# MICROCONTROLER.net
KiCad netlist of a schematic drawn in Altium Designer
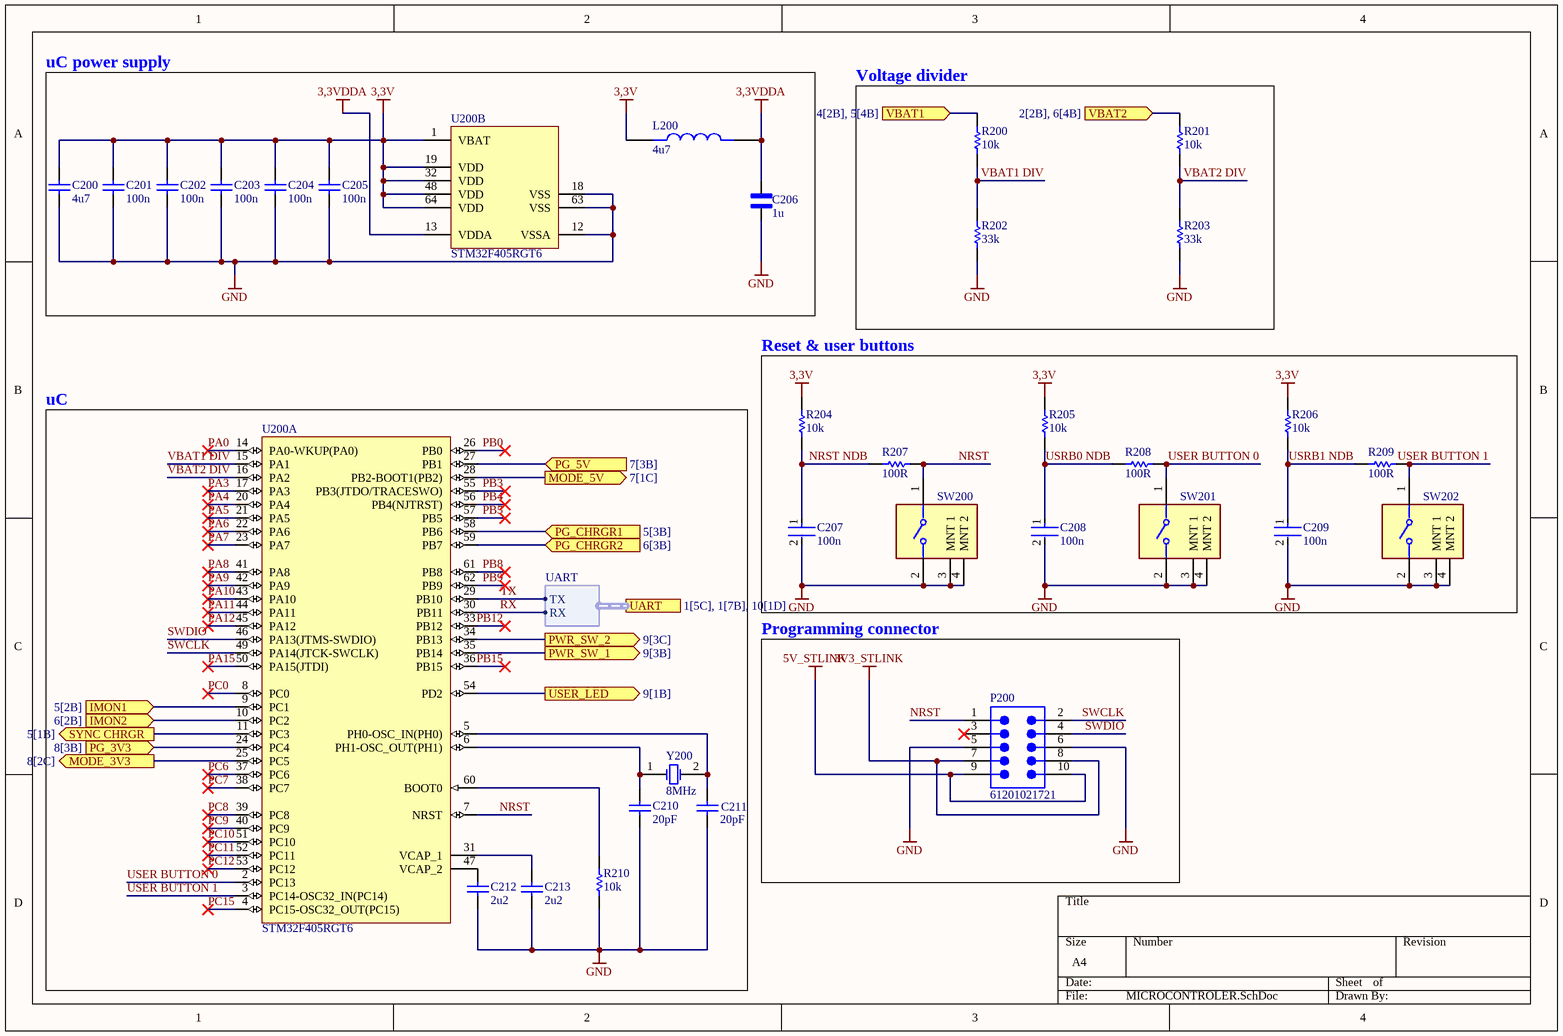
[diagram p0: MICROCONTROLER.SchDoc]

(export (version "E")
  (design (tool "Eeschema 10.0.6"))
  (components
    (comp (ref "C200")
      (value "4u7")
      (footprint "CAPC1005X55X30LL05T10")
      (fields (field (name "MANUFACTURER") "Kemet") (field (name "PART NUMBER") "C0402C104K4RACTU"))
      (libsource (lib "Altium Content Vault") (part "CAP"))
    )
    (comp (ref "C201")
      (value "100n")
      (footprint "CAPC1005X55X30LL05T10")
      (fields (field (name "MANUFACTURER") "Kemet") (field (name "PART NUMBER") "C0402C104K4RACTU"))
      (libsource (lib "Altium Content Vault") (part "CAP"))
    )
    (comp (ref "C202")
      (value "100n")
      (footprint "CAPC1005X55X30LL05T10")
      (fields (field (name "MANUFACTURER") "Kemet") (field (name "PART NUMBER") "C0402C104K4RACTU"))
      (libsource (lib "Altium Content Vault") (part "CAP"))
    )
    (comp (ref "C203")
      (value "100n")
      (footprint "CAPC1005X55X30LL05T10")
      (fields (field (name "MANUFACTURER") "Kemet") (field (name "PART NUMBER") "C0402C104K4RACTU"))
      (libsource (lib "Altium Content Vault") (part "CAP"))
    )
    (comp (ref "C204")
      (value "100n")
      (footprint "CAPC1005X55X30LL05T10")
      (fields (field (name "MANUFACTURER") "Kemet") (field (name "PART NUMBER") "C0402C104K4RACTU"))
      (libsource (lib "Altium Content Vault") (part "CAP"))
    )
    (comp (ref "C205")
      (value "100n")
      (footprint "CAPC1005X55X30LL05T10")
      (fields (field (name "MANUFACTURER") "Kemet") (field (name "PART NUMBER") "C0402C104K4RACTU"))
      (libsource (lib "Altium Content Vault") (part "CAP"))
    )
    (comp (ref "C206")
      (value "1u")
      (footprint "CAPC1005X70N")
      (fields (field (name "MF") "Taiyo Yuden") (field (name "MP") "MAASL105CD7105MFCA01"))
      (libsource (lib "C_1u") (part "MAASL105CD7105MFCA01"))
    )
    (comp (ref "C207")
      (value "100n")
      (footprint "FP-C0402-BB-MFG")
      (description "CAP CER 0.1UF 10V X5R 0402")
      (fields (field (name "MANUFACTURER") "Kemet") (field (name "TOLERANCE") "0.1"))
      (libsource (lib "Altium Content Vault") (part "b4654b650e69147ec39a6b967a45e02"))
    )
    (comp (ref "C208")
      (value "100n")
      (footprint "FP-C0402-BB-MFG")
      (description "CAP CER 0.1UF 10V X5R 0402")
      (fields (field (name "MANUFACTURER") "Kemet") (field (name "TOLERANCE") "0.1"))
      (libsource (lib "Altium Content Vault") (part "b4654b650e69147ec39a6b967a45e02"))
    )
    (comp (ref "C209")
      (value "100n")
      (footprint "FP-C0402-BB-MFG")
      (description "CAP CER 0.1UF 10V X5R 0402")
      (fields (field (name "MANUFACTURER") "Kemet") (field (name "TOLERANCE") "0.1"))
      (libsource (lib "Altium Content Vault") (part "b4654b650e69147ec39a6b967a45e02"))
    )
    (comp (ref "C210")
      (value "20pF")
      (footprint "tu 0805")
      (description "Dán")
      (libsource (lib "Capacitor") (part "Tu 0805 20pF 50V 10%"))
    )
    (comp (ref "C211")
      (value "20pF")
      (footprint "tu 0805")
      (description "Dán")
      (libsource (lib "Capacitor") (part "Tu 0805 20pF 50V 10%"))
    )
    (comp (ref "C212")
      (value "2u2")
      (footprint "tu 0805")
      (description "Dán")
      (libsource (lib "Capacitor") (part "Tu 0805 225 25V 10%"))
    )
    (comp (ref "C213")
      (value "2u2")
      (footprint "tu 0805")
      (description "Dán")
      (libsource (lib "Capacitor") (part "Tu 0805 225 25V 10%"))
    )
    (comp (ref "L200")
      (value "4u7")
      (footprint "INDC2012X100N")
      (description "Surface Mount High Frequency Inductor, MLP Series, 4.7 H, 20%, 0805 [2012 Metric], 0.26 ohm")
      (fields (field (name "MF") "TDK") (field (name "MP") "MLP2012S4R7MT0S1"))
      (libsource (lib "L4u7") (part "MLP2012S4R7MT0S1"))
    )
    (comp (ref "P200")
      (value "61201021721")
      (footprint "61201021721")
      (libsource (lib "Altium Content Vault") (part "Header_Male_2R_10P"))
    )
    (comp (ref "R200")
      (value "10k")
      (footprint "RESC1609X50X30NL8T20")
      (description "Chip Resistor, 10 KOhm, +/- 1%, 100 mW, -55 to 155 degC, 0603 (1608 Metric), RoHS, Tape and Reel")
      (fields (field (name "MANUFACTURER") "Vishay Semiconductor"))
      (libsource (lib "Altium Content Vault") (part "RES-2"))
    )
    (comp (ref "R201")
      (value "10k")
      (footprint "RESC1609X50X30NL8T20")
      (description "Chip Resistor, 10 KOhm, +/- 1%, 100 mW, -55 to 155 degC, 0603 (1608 Metric), RoHS, Tape and Reel")
      (fields (field (name "MANUFACTURER") "Vishay Semiconductor"))
      (libsource (lib "Altium Content Vault") (part "RES-2"))
    )
    (comp (ref "R202")
      (value "33k")
      (footprint "RESC1005X40X25ML05T10")
      (fields (field (name "PART NUMBER") "RC0402FR-0733KL") (field (name "MANUFACTURER") "Yageo / Phycomp"))
      (libsource (lib "Altium Content Vault") (part "RES"))
    )
    (comp (ref "R203")
      (value "33k")
      (footprint "RESC1005X40X25ML05T10")
      (fields (field (name "PART NUMBER") "RC0402FR-0733KL") (field (name "MANUFACTURER") "Yageo / Phycomp"))
      (libsource (lib "Altium Content Vault") (part "RES"))
    )
    (comp (ref "R204")
      (value "10k")
      (footprint "RESC1609X50X30NL8T20")
      (description "Chip Resistor, 10 KOhm, +/- 1%, 100 mW, -55 to 155 degC, 0603 (1608 Metric), RoHS, Tape and Reel")
      (fields (field (name "MANUFACTURER") "Vishay Semiconductor"))
      (libsource (lib "Altium Content Vault") (part "RES-2"))
    )
    (comp (ref "R205")
      (value "10k")
      (footprint "RESC1609X50X30NL8T20")
      (description "Chip Resistor, 10 KOhm, +/- 1%, 100 mW, -55 to 155 degC, 0603 (1608 Metric), RoHS, Tape and Reel")
      (fields (field (name "MANUFACTURER") "Vishay Semiconductor"))
      (libsource (lib "Altium Content Vault") (part "RES-2"))
    )
    (comp (ref "R206")
      (value "10k")
      (footprint "RESC1609X50X30NL8T20")
      (description "Chip Resistor, 10 KOhm, +/- 1%, 100 mW, -55 to 155 degC, 0603 (1608 Metric), RoHS, Tape and Reel")
      (fields (field (name "MANUFACTURER") "Vishay Semiconductor"))
      (libsource (lib "Altium Content Vault") (part "RES-2"))
    )
    (comp (ref "R207")
      (value "100R")
      (footprint "RESC1005X40X25ML05T10")
      (fields (field (name "PART NUMBER") "RC0402FR-07100RL") (field (name "MANUFACTURER") "Yageo / Phycomp"))
      (libsource (lib "Altium Content Vault") (part "RES"))
    )
    (comp (ref "R208")
      (value "100R")
      (footprint "RESC1005X40X25ML05T10")
      (fields (field (name "PART NUMBER") "RC0402FR-07100RL") (field (name "MANUFACTURER") "Yageo / Phycomp"))
      (libsource (lib "Altium Content Vault") (part "RES"))
    )
    (comp (ref "R209")
      (value "100R")
      (footprint "RESC1005X40X25ML05T10")
      (fields (field (name "PART NUMBER") "RC0402FR-07100RL") (field (name "MANUFACTURER") "Yageo / Phycomp"))
      (libsource (lib "Altium Content Vault") (part "RES"))
    )
    (comp (ref "R210")
      (value "10k")
      (footprint "RESC1609X50X30NL8T20")
      (description "Chip Resistor, 10 KOhm, +/- 1%, 100 mW, -55 to 155 degC, 0603 (1608 Metric), RoHS, Tape and Reel")
      (fields (field (name "MANUFACTURER") "Vishay Semiconductor"))
      (libsource (lib "Altium Content Vault") (part "RES-2"))
    )
    (comp (ref "SW200")
      (value "B3F-3152")
      (footprint "FP-B3F-3152-MFG")
      (description "SWITCH TACTILE SPST-NO 0.05A 24V")
      (libsource (lib "Altium Content Vault") (part "ed2974a2078be5bbdf800c999931250"))
    )
    (comp (ref "SW201")
      (value "B3F-3152")
      (footprint "FP-B3F-3152-MFG")
      (description "SWITCH TACTILE SPST-NO 0.05A 24V")
      (libsource (lib "Altium Content Vault") (part "ed2974a2078be5bbdf800c999931250"))
    )
    (comp (ref "SW202")
      (value "B3F-3152")
      (footprint "FP-B3F-3152-MFG")
      (description "SWITCH TACTILE SPST-NO 0.05A 24V")
      (libsource (lib "Altium Content Vault") (part "ed2974a2078be5bbdf800c999931250"))
    )
    (comp (ref "U200")
      (value "STM32F405RGT6")
      (footprint "STM-LQFP64_N")
      (fields (field (name "MANUFACTURER") "STMicroelectronics"))
      (libsource (lib "Altium Content Vault") (part "MC-ARM-STM32F4X5-SQ64"))
    )
    (comp (ref "Y200")
      (value "8MHz")
      (footprint "ABRA-ABLS-14.7456MHZ-B2-T_V")
      (description "Low Profile Crystal, 8.0 MHz, +/- 30 ppm, -20 to 70 degC, 2-Pin SMD, RoHS, Tape and Reel")
      (fields (field (name "MANUFACTURER") "ABRACON") (field (name "TOLERANCE") "30PPM"))
      (libsource (lib "Altium Content Vault") (part "XTAL_1-2-2"))
    )
  )
  (nets
    (net (code "2") (name "/IMON1") (class "Default")
      (node (ref "U200") (pin "9") (pinfunction "PC1_9") (pintype "bidirectional"))
    )
    (net (code "3") (name "/IMON2") (class "Default")
      (node (ref "U200") (pin "10") (pinfunction "PC2_10") (pintype "bidirectional"))
    )
    (net (code "4") (name "/MODE_3V3") (class "Default")
      (node (ref "U200") (pin "25") (pinfunction "PC5_25") (pintype "bidirectional"))
    )
    (net (code "5") (name "/MODE_5V") (class "Default")
      (node (ref "U200") (pin "28") (pinfunction "PB2-BOOT1(PB2)_28") (pintype "bidirectional"))
    )
    (net (code "6") (name "/NRST") (class "Default")
      (node (ref "P200") (pin "1") (pinfunction "1_1") (pintype "passive"))
      (node (ref "R207") (pin "2") (pinfunction "2_2") (pintype "passive"))
      (node (ref "SW200") (pin "1") (pinfunction "1_1") (pintype "passive"))
      (node (ref "U200") (pin "7") (pinfunction "NRST_7") (pintype "bidirectional"))
    )
    (net (code "7") (name "/NRST NDB") (class "Default")
      (node (ref "C207") (pin "1") (pinfunction "1_1") (pintype "passive"))
      (node (ref "R204") (pin "1") (pinfunction "1_1") (pintype "passive"))
      (node (ref "R207") (pin "1") (pinfunction "1_1") (pintype "passive"))
    )
    (net (code "8") (name "/PA0") (class "Default")
      (node (ref "U200") (pin "14") (pinfunction "PA0-WKUP(PA0)_14") (pintype "bidirectional+no_connect"))
    )
    (net (code "9") (name "/PA3") (class "Default")
      (node (ref "U200") (pin "17") (pinfunction "PA3_17") (pintype "bidirectional+no_connect"))
    )
    (net (code "10") (name "/PA4") (class "Default")
      (node (ref "U200") (pin "20") (pinfunction "PA4_20") (pintype "bidirectional+no_connect"))
    )
    (net (code "11") (name "/PA5") (class "Default")
      (node (ref "U200") (pin "21") (pinfunction "PA5_21") (pintype "bidirectional+no_connect"))
    )
    (net (code "12") (name "/PA6") (class "Default")
      (node (ref "U200") (pin "22") (pinfunction "PA6_22") (pintype "bidirectional+no_connect"))
    )
    (net (code "13") (name "/PA7") (class "Default")
      (node (ref "U200") (pin "23") (pinfunction "PA7_23") (pintype "bidirectional+no_connect"))
    )
    (net (code "14") (name "/PA8") (class "Default")
      (node (ref "U200") (pin "41") (pinfunction "PA8_41") (pintype "bidirectional+no_connect"))
    )
    (net (code "15") (name "/PA9") (class "Default")
      (node (ref "U200") (pin "42") (pinfunction "PA9_42") (pintype "bidirectional+no_connect"))
    )
    (net (code "16") (name "/PA10") (class "Default")
      (node (ref "U200") (pin "43") (pinfunction "PA10_43") (pintype "bidirectional+no_connect"))
    )
    (net (code "17") (name "/PA11") (class "Default")
      (node (ref "U200") (pin "44") (pinfunction "PA11_44") (pintype "bidirectional+no_connect"))
    )
    (net (code "18") (name "/PA12") (class "Default")
      (node (ref "U200") (pin "45") (pinfunction "PA12_45") (pintype "bidirectional+no_connect"))
    )
    (net (code "19") (name "/PA15") (class "Default")
      (node (ref "U200") (pin "50") (pinfunction "PA15(JTDI)_50") (pintype "bidirectional+no_connect"))
    )
    (net (code "20") (name "/PB0") (class "Default")
      (node (ref "U200") (pin "26") (pinfunction "PB0_26") (pintype "bidirectional+no_connect"))
    )
    (net (code "21") (name "/PB3") (class "Default")
      (node (ref "U200") (pin "55") (pinfunction "PB3(JTDO/TRACESWO)_55") (pintype "bidirectional+no_connect"))
    )
    (net (code "22") (name "/PB4") (class "Default")
      (node (ref "U200") (pin "56") (pinfunction "PB4(NJTRST)_56") (pintype "bidirectional+no_connect"))
    )
    (net (code "23") (name "/PB5") (class "Default")
      (node (ref "U200") (pin "57") (pinfunction "PB5_57") (pintype "bidirectional+no_connect"))
    )
    (net (code "24") (name "/PB8") (class "Default")
      (node (ref "U200") (pin "61") (pinfunction "PB8_61") (pintype "bidirectional+no_connect"))
    )
    (net (code "25") (name "/PB9") (class "Default")
      (node (ref "U200") (pin "62") (pinfunction "PB9_62") (pintype "bidirectional+no_connect"))
    )
    (net (code "26") (name "/PB12") (class "Default")
      (node (ref "U200") (pin "33") (pinfunction "PB12_33") (pintype "bidirectional+no_connect"))
    )
    (net (code "27") (name "/PB15") (class "Default")
      (node (ref "U200") (pin "36") (pinfunction "PB15_36") (pintype "bidirectional+no_connect"))
    )
    (net (code "28") (name "/PC0") (class "Default")
      (node (ref "U200") (pin "8") (pinfunction "PC0_8") (pintype "bidirectional+no_connect"))
    )
    (net (code "29") (name "/PC6") (class "Default")
      (node (ref "U200") (pin "37") (pinfunction "PC6_37") (pintype "bidirectional+no_connect"))
    )
    (net (code "30") (name "/PC7") (class "Default")
      (node (ref "U200") (pin "38") (pinfunction "PC7_38") (pintype "bidirectional+no_connect"))
    )
    (net (code "31") (name "/PC8") (class "Default")
      (node (ref "U200") (pin "39") (pinfunction "PC8_39") (pintype "bidirectional+no_connect"))
    )
    (net (code "32") (name "/PC9") (class "Default")
      (node (ref "U200") (pin "40") (pinfunction "PC9_40") (pintype "bidirectional+no_connect"))
    )
    (net (code "33") (name "/PC10") (class "Default")
      (node (ref "U200") (pin "51") (pinfunction "PC10_51") (pintype "bidirectional+no_connect"))
    )
    (net (code "34") (name "/PC11") (class "Default")
      (node (ref "U200") (pin "52") (pinfunction "PC11_52") (pintype "bidirectional+no_connect"))
    )
    (net (code "35") (name "/PC12") (class "Default")
      (node (ref "U200") (pin "53") (pinfunction "PC12_53") (pintype "bidirectional+no_connect"))
    )
    (net (code "36") (name "/PC15") (class "Default")
      (node (ref "U200") (pin "4") (pinfunction "PC15-OSC32_OUT(PC15)_4") (pintype "bidirectional+no_connect"))
    )
    (net (code "37") (name "/PG_3V3") (class "Default")
      (node (ref "U200") (pin "24") (pinfunction "PC4_24") (pintype "bidirectional"))
    )
    (net (code "38") (name "/PG_5V") (class "Default")
      (node (ref "U200") (pin "27") (pinfunction "PB1_27") (pintype "bidirectional"))
    )
    (net (code "39") (name "/PG_CHRGR1") (class "Default")
      (node (ref "U200") (pin "58") (pinfunction "PB6_58") (pintype "bidirectional"))
    )
    (net (code "40") (name "/PG_CHRGR2") (class "Default")
      (node (ref "U200") (pin "59") (pinfunction "PB7_59") (pintype "bidirectional"))
    )
    (net (code "41") (name "/PWR_SW_1") (class "Default")
      (node (ref "U200") (pin "35") (pinfunction "PB14_35") (pintype "bidirectional"))
    )
    (net (code "42") (name "/PWR_SW_2") (class "Default")
      (node (ref "U200") (pin "34") (pinfunction "PB13_34") (pintype "bidirectional"))
    )
    (net (code "43") (name "/RX") (class "Default")
      (node (ref "U200") (pin "30") (pinfunction "PB11_30") (pintype "bidirectional"))
    )
    (net (code "44") (name "/SWCLK") (class "Default")
      (node (ref "P200") (pin "2") (pinfunction "2_2") (pintype "passive"))
      (node (ref "U200") (pin "49") (pinfunction "PA14(JTCK-SWCLK)_49") (pintype "bidirectional"))
    )
    (net (code "45") (name "/SWDIO") (class "Default")
      (node (ref "P200") (pin "4") (pinfunction "4_4") (pintype "passive"))
      (node (ref "U200") (pin "46") (pinfunction "PA13(JTMS-SWDIO)_46") (pintype "bidirectional"))
    )
    (net (code "46") (name "/SYNC CHRGR") (class "Default")
      (node (ref "U200") (pin "11") (pinfunction "PC3_11") (pintype "bidirectional"))
    )
    (net (code "47") (name "/TX") (class "Default")
      (node (ref "U200") (pin "29") (pinfunction "PB10_29") (pintype "bidirectional"))
    )
    (net (code "48") (name "/USER BUTTON 0") (class "Default")
      (node (ref "R208") (pin "2") (pinfunction "2_2") (pintype "passive"))
      (node (ref "SW201") (pin "1") (pinfunction "1_1") (pintype "passive"))
      (node (ref "U200") (pin "2") (pinfunction "PC13_2") (pintype "bidirectional"))
    )
    (net (code "49") (name "/USER BUTTON 1") (class "Default")
      (node (ref "R209") (pin "2") (pinfunction "2_2") (pintype "passive"))
      (node (ref "SW202") (pin "1") (pinfunction "1_1") (pintype "passive"))
      (node (ref "U200") (pin "3") (pinfunction "PC14-OSC32_IN(PC14)_3") (pintype "bidirectional"))
    )
    (net (code "50") (name "/USER_LED") (class "Default")
      (node (ref "U200") (pin "54") (pinfunction "PD2_54") (pintype "bidirectional"))
    )
    (net (code "51") (name "/USRB0 NDB") (class "Default")
      (node (ref "C208") (pin "1") (pinfunction "1_1") (pintype "passive"))
      (node (ref "R205") (pin "1") (pinfunction "1_1") (pintype "passive"))
      (node (ref "R208") (pin "1") (pinfunction "1_1") (pintype "passive"))
    )
    (net (code "52") (name "/USRB1 NDB") (class "Default")
      (node (ref "C209") (pin "1") (pinfunction "1_1") (pintype "passive"))
      (node (ref "R206") (pin "1") (pinfunction "1_1") (pintype "passive"))
      (node (ref "R209") (pin "1") (pinfunction "1_1") (pintype "passive"))
    )
    (net (code "53") (name "/VBAT1") (class "Default")
      (node (ref "R200") (pin "2") (pinfunction "2_2") (pintype "passive"))
    )
    (net (code "54") (name "/VBAT1 DIV") (class "Default")
      (node (ref "R200") (pin "1") (pinfunction "1_1") (pintype "passive"))
      (node (ref "R202") (pin "2") (pinfunction "2_2") (pintype "passive"))
      (node (ref "U200") (pin "15") (pinfunction "PA1_15") (pintype "bidirectional"))
    )
    (net (code "55") (name "/VBAT2") (class "Default")
      (node (ref "R201") (pin "2") (pinfunction "2_2") (pintype "passive"))
    )
    (net (code "56") (name "/VBAT2 DIV") (class "Default")
      (node (ref "R201") (pin "1") (pinfunction "1_1") (pintype "passive"))
      (node (ref "R203") (pin "2") (pinfunction "2_2") (pintype "passive"))
      (node (ref "U200") (pin "16") (pinfunction "PA2_16") (pintype "bidirectional"))
    )
    (net (code "58") (name "3,3V") (class "Default")
      (node (ref "C200") (pin "2") (pinfunction "2_2") (pintype "passive"))
      (node (ref "C201") (pin "2") (pinfunction "2_2") (pintype "passive"))
      (node (ref "C202") (pin "2") (pinfunction "2_2") (pintype "passive"))
      (node (ref "C203") (pin "2") (pinfunction "2_2") (pintype "passive"))
      (node (ref "C204") (pin "2") (pinfunction "2_2") (pintype "passive"))
      (node (ref "C205") (pin "2") (pinfunction "2_2") (pintype "passive"))
      (node (ref "L200") (pin "1") (pinfunction "1_1") (pintype "passive"))
      (node (ref "R204") (pin "2") (pinfunction "2_2") (pintype "passive"))
      (node (ref "R205") (pin "2") (pinfunction "2_2") (pintype "passive"))
      (node (ref "R206") (pin "2") (pinfunction "2_2") (pintype "passive"))
      (node (ref "U200") (pin "1") (pinfunction "VBAT_1") (pintype "power_in"))
      (node (ref "U200") (pin "19") (pinfunction "VDD_19") (pintype "power_in"))
      (node (ref "U200") (pin "32") (pinfunction "VDD_32") (pintype "power_in"))
      (node (ref "U200") (pin "48") (pinfunction "VDD_48") (pintype "power_in"))
      (node (ref "U200") (pin "64") (pinfunction "VDD_64") (pintype "power_in"))
    )
    (net (code "59") (name "3,3VDDA") (class "Default")
      (node (ref "C206") (pin "2") (pinfunction "2_2") (pintype "passive"))
      (node (ref "L200") (pin "2") (pinfunction "2_2") (pintype "passive"))
      (node (ref "U200") (pin "13") (pinfunction "VDDA_13") (pintype "power_in"))
    )
    (net (code "60") (name "3V3_STLINK") (class "Default")
      (node (ref "P200") (pin "7") (pinfunction "7_7") (pintype "passive"))
      (node (ref "P200") (pin "8") (pinfunction "8_8") (pintype "passive"))
    )
    (net (code "61") (name "5V_STLINK") (class "Default")
      (node (ref "P200") (pin "10") (pinfunction "10_10") (pintype "passive"))
      (node (ref "P200") (pin "9") (pinfunction "9_9") (pintype "passive"))
    )
    (net (code "62") (name "GND") (class "Default")
      (node (ref "C200") (pin "1") (pinfunction "1_1") (pintype "passive"))
      (node (ref "C201") (pin "1") (pinfunction "1_1") (pintype "passive"))
      (node (ref "C202") (pin "1") (pinfunction "1_1") (pintype "passive"))
      (node (ref "C203") (pin "1") (pinfunction "1_1") (pintype "passive"))
      (node (ref "C204") (pin "1") (pinfunction "1_1") (pintype "passive"))
      (node (ref "C205") (pin "1") (pinfunction "1_1") (pintype "passive"))
      (node (ref "C206") (pin "1") (pinfunction "1_1") (pintype "passive"))
      (node (ref "C207") (pin "2") (pinfunction "2_2") (pintype "passive"))
      (node (ref "C208") (pin "2") (pinfunction "2_2") (pintype "passive"))
      (node (ref "C209") (pin "2") (pinfunction "2_2") (pintype "passive"))
      (node (ref "C210") (pin "2") (pinfunction "2_2") (pintype "passive"))
      (node (ref "C211") (pin "2") (pinfunction "2_2") (pintype "passive"))
      (node (ref "C212") (pin "2") (pinfunction "2_2") (pintype "passive"))
      (node (ref "C213") (pin "2") (pinfunction "2_2") (pintype "passive"))
      (node (ref "P200") (pin "5") (pinfunction "5_5") (pintype "passive"))
      (node (ref "P200") (pin "6") (pinfunction "6_6") (pintype "passive"))
      (node (ref "R202") (pin "1") (pinfunction "1_1") (pintype "passive"))
      (node (ref "R203") (pin "1") (pinfunction "1_1") (pintype "passive"))
      (node (ref "R210") (pin "1") (pinfunction "1_1") (pintype "passive"))
      (node (ref "SW200") (pin "2") (pinfunction "2_2") (pintype "passive"))
      (node (ref "SW200") (pin "3") (pinfunction "MNT_1_3") (pintype "passive"))
      (node (ref "SW200") (pin "4") (pinfunction "MNT_2_4") (pintype "passive"))
      (node (ref "SW201") (pin "2") (pinfunction "2_2") (pintype "passive"))
      (node (ref "SW201") (pin "3") (pinfunction "MNT_1_3") (pintype "passive"))
      (node (ref "SW201") (pin "4") (pinfunction "MNT_2_4") (pintype "passive"))
      (node (ref "SW202") (pin "2") (pinfunction "2_2") (pintype "passive"))
      (node (ref "SW202") (pin "3") (pinfunction "MNT_1_3") (pintype "passive"))
      (node (ref "SW202") (pin "4") (pinfunction "MNT_2_4") (pintype "passive"))
      (node (ref "U200") (pin "12") (pinfunction "VSSA_12") (pintype "power_in"))
      (node (ref "U200") (pin "18") (pinfunction "VSS_18") (pintype "power_in"))
      (node (ref "U200") (pin "63") (pinfunction "VSS_63") (pintype "power_in"))
    )
    (net (code "63") (name "Net-(U200A-BOOT0)") (class "Default")
      (node (ref "R210") (pin "2") (pinfunction "2_2") (pintype "passive"))
      (node (ref "U200") (pin "60") (pinfunction "BOOT0_60") (pintype "input"))
    )
    (net (code "64") (name "Net-(U200A-PH0-OSC_IN(PH0))") (class "Default")
      (node (ref "C211") (pin "1") (pinfunction "1_1") (pintype "passive"))
      (node (ref "U200") (pin "5") (pinfunction "PH0-OSC_IN(PH0)_5") (pintype "bidirectional"))
      (node (ref "Y200") (pin "2") (pinfunction "X2_2") (pintype "passive"))
    )
    (net (code "65") (name "Net-(U200A-PH1-OSC_OUT(PH1))") (class "Default")
      (node (ref "C210") (pin "1") (pinfunction "1_1") (pintype "passive"))
      (node (ref "U200") (pin "6") (pinfunction "PH1-OSC_OUT(PH1)_6") (pintype "bidirectional"))
      (node (ref "Y200") (pin "1") (pinfunction "X1_1") (pintype "passive"))
    )
    (net (code "66") (name "Net-(U200A-VCAP_1)") (class "Default")
      (node (ref "C213") (pin "1") (pinfunction "1_1") (pintype "passive"))
      (node (ref "U200") (pin "31") (pinfunction "VCAP_1_31") (pintype "power_in"))
    )
    (net (code "67") (name "Net-(U200A-VCAP_2)") (class "Default")
      (node (ref "C212") (pin "1") (pinfunction "1_1") (pintype "passive"))
      (node (ref "U200") (pin "47") (pinfunction "VCAP_2_47") (pintype "power_in"))
    )
    (net (code "68") (name "unconnected-(P200-Pad3)") (class "Default")
      (node (ref "P200") (pin "3") (pinfunction "3_3") (pintype "passive+no_connect"))
    )
  )
)
